# Comparator.net
KiCad netlist of a schematic drawn in EAGLE
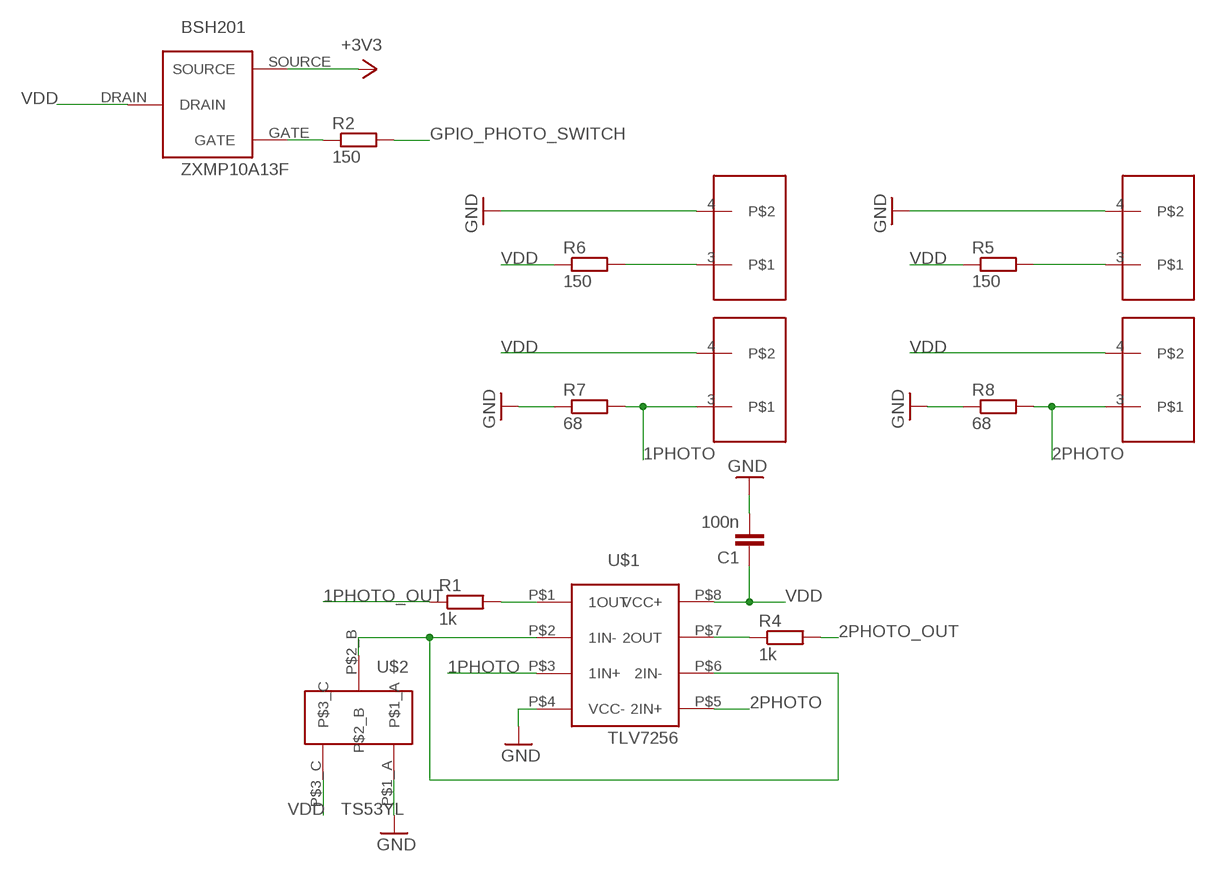
[diagram p0: schematic, sheet 1]

(export (version "E")
  (design (tool "Eeschema 10.0.6"))
  (components
    (comp (ref "BSH201")
      (value "ZXMP10A13F")
      (footprint "eagle-import:P-CHANNEL")
      (libsource (lib "eagle-import") (part "ZXMP10A13F"))
    )
    (comp (ref "C1")
      (value "100n")
      (footprint "eagle-import:C0805")
      (libsource (lib "eagle-import") (part "C-EUC0805"))
    )
    (comp (ref "R1")
      (value "1k")
      (footprint "eagle-import:R0805")
      (libsource (lib "eagle-import") (part "R-EU_R0805"))
    )
    (comp (ref "R2")
      (value "150")
      (footprint "eagle-import:R0805")
      (libsource (lib "eagle-import") (part "R-EU_R0805"))
    )
    (comp (ref "R4")
      (value "1k")
      (footprint "eagle-import:R0805")
      (libsource (lib "eagle-import") (part "R-EU_R0805"))
    )
    (comp (ref "R5")
      (value "150")
      (footprint "eagle-import:R0805")
      (libsource (lib "eagle-import") (part "R-EU_R0805"))
    )
    (comp (ref "R6")
      (value "150")
      (footprint "eagle-import:R0805")
      (libsource (lib "eagle-import") (part "R-EU_R0805"))
    )
    (comp (ref "R7")
      (value "68")
      (footprint "eagle-import:R0805")
      (libsource (lib "eagle-import") (part "R-EU_R0805"))
    )
    (comp (ref "R8")
      (value "68")
      (footprint "eagle-import:R0805")
      (libsource (lib "eagle-import") (part "R-EU_R0805"))
    )
    (comp (ref "SKRUVPLINT_2P1")
      (value "SKRUVPLINT_2P")
      (footprint "eagle-import:SKRUVPLINT_2P")
      (libsource (lib "eagle-import") (part "SKRUVPLINT_2P"))
    )
    (comp (ref "SKRUVPLINT_2P2")
      (value "SKRUVPLINT_2P")
      (footprint "eagle-import:SKRUVPLINT_2P")
      (libsource (lib "eagle-import") (part "SKRUVPLINT_2P"))
    )
    (comp (ref "SKRUVPLINT_2P3")
      (value "SKRUVPLINT_2P")
      (footprint "eagle-import:SKRUVPLINT_2P")
      (libsource (lib "eagle-import") (part "SKRUVPLINT_2P"))
    )
    (comp (ref "SKRUVPLINT_2P4")
      (value "SKRUVPLINT_2P")
      (footprint "eagle-import:SKRUVPLINT_2P")
      (libsource (lib "eagle-import") (part "SKRUVPLINT_2P"))
    )
    (comp (ref "U$1")
      (value "TLV7256")
      (footprint "eagle-import:VSSOP")
      (libsource (lib "eagle-import") (part "TLV7256"))
    )
    (comp (ref "U$2")
      (value "TS53YL")
      (footprint "eagle-import:POT")
      (libsource (lib "eagle-import") (part "TS53YL"))
    )
  )
  (nets
    (net (code "1") (name "+3V3") (class "Default")
      (node (ref "BSH201") (pin "SOURCE") (pinfunction "SOURCE_SOURCE") (pintype "bidirectional"))
    )
    (net (code "2") (name "/1PHOTO") (class "Default")
      (node (ref "R7") (pin "2") (pinfunction "2_2") (pintype "passive"))
      (node (ref "SKRUVPLINT_2P2") (pin "3") (pinfunction "P$1_3") (pintype "bidirectional"))
      (node (ref "U$1") (pin "P$3") (pinfunction "1IN+_P$3") (pintype "bidirectional"))
    )
    (net (code "3") (name "/1PHOTO_OUT") (class "Default")
      (node (ref "R1") (pin "1") (pinfunction "1_1") (pintype "passive"))
    )
    (net (code "4") (name "/2PHOTO") (class "Default")
      (node (ref "R8") (pin "2") (pinfunction "2_2") (pintype "passive"))
      (node (ref "SKRUVPLINT_2P4") (pin "3") (pinfunction "P$1_3") (pintype "bidirectional"))
      (node (ref "U$1") (pin "P$5") (pinfunction "2IN+_P$5") (pintype "bidirectional"))
    )
    (net (code "5") (name "/2PHOTO_OUT") (class "Default")
      (node (ref "R4") (pin "2") (pinfunction "2_2") (pintype "passive"))
    )
    (net (code "6") (name "/GPIO_PHOTO_SWITCH") (class "Default")
      (node (ref "R2") (pin "2") (pinfunction "2_2") (pintype "passive"))
    )
    (net (code "7") (name "/VDD") (class "Default")
      (node (ref "BSH201") (pin "DRAIN") (pinfunction "DRAIN_DRAIN") (pintype "bidirectional"))
      (node (ref "C1") (pin "1") (pinfunction "1_1") (pintype "passive"))
      (node (ref "R5") (pin "1") (pinfunction "1_1") (pintype "passive"))
      (node (ref "R6") (pin "1") (pinfunction "1_1") (pintype "passive"))
      (node (ref "SKRUVPLINT_2P2") (pin "4") (pinfunction "P$2_4") (pintype "bidirectional"))
      (node (ref "SKRUVPLINT_2P4") (pin "4") (pinfunction "P$2_4") (pintype "bidirectional"))
      (node (ref "U$1") (pin "P$8") (pinfunction "VCC+_P$8") (pintype "bidirectional"))
      (node (ref "U$2") (pin "P$3_C") (pinfunction "P$3_C_P$3_C") (pintype "bidirectional"))
    )
    (net (code "8") (name "GND") (class "Default")
      (node (ref "C1") (pin "2") (pinfunction "2_2") (pintype "passive"))
      (node (ref "R7") (pin "1") (pinfunction "1_1") (pintype "passive"))
      (node (ref "R8") (pin "1") (pinfunction "1_1") (pintype "passive"))
      (node (ref "SKRUVPLINT_2P1") (pin "4") (pinfunction "P$2_4") (pintype "bidirectional"))
      (node (ref "SKRUVPLINT_2P3") (pin "4") (pinfunction "P$2_4") (pintype "bidirectional"))
      (node (ref "U$1") (pin "P$4") (pinfunction "VCC-_P$4") (pintype "bidirectional"))
      (node (ref "U$2") (pin "P$1_A") (pinfunction "P$1_A_P$1_A") (pintype "bidirectional"))
    )
    (net (code "9") (name "Net-(BSH201-PadGATE)") (class "Default")
      (node (ref "BSH201") (pin "GATE") (pinfunction "GATE_GATE") (pintype "bidirectional"))
      (node (ref "R2") (pin "1") (pinfunction "1_1") (pintype "passive"))
    )
    (net (code "10") (name "Net-(SKRUVPLINT_2P1-P$1)") (class "Default")
      (node (ref "R6") (pin "2") (pinfunction "2_2") (pintype "passive"))
      (node (ref "SKRUVPLINT_2P1") (pin "3") (pinfunction "P$1_3") (pintype "bidirectional"))
    )
    (net (code "11") (name "Net-(SKRUVPLINT_2P3-P$1)") (class "Default")
      (node (ref "R5") (pin "2") (pinfunction "2_2") (pintype "passive"))
      (node (ref "SKRUVPLINT_2P3") (pin "3") (pinfunction "P$1_3") (pintype "bidirectional"))
    )
    (net (code "12") (name "Net-(U$1-1IN-)") (class "Default")
      (node (ref "U$1") (pin "P$2") (pinfunction "1IN-_P$2") (pintype "bidirectional"))
      (node (ref "U$1") (pin "P$6") (pinfunction "2IN-_P$6") (pintype "bidirectional"))
      (node (ref "U$2") (pin "P$2_B") (pinfunction "P$2_B_P$2_B") (pintype "bidirectional"))
    )
    (net (code "13") (name "Net-(U$1-1OUT)") (class "Default")
      (node (ref "R1") (pin "2") (pinfunction "2_2") (pintype "passive"))
      (node (ref "U$1") (pin "P$1") (pinfunction "1OUT_P$1") (pintype "bidirectional"))
    )
    (net (code "14") (name "Net-(U$1-2OUT)") (class "Default")
      (node (ref "R4") (pin "1") (pinfunction "1_1") (pintype "passive"))
      (node (ref "U$1") (pin "P$7") (pinfunction "2OUT_P$7") (pintype "bidirectional"))
    )
  )
)
